# RMP_MAIN.net
KiCad netlist of a schematic drawn in Altium Designer
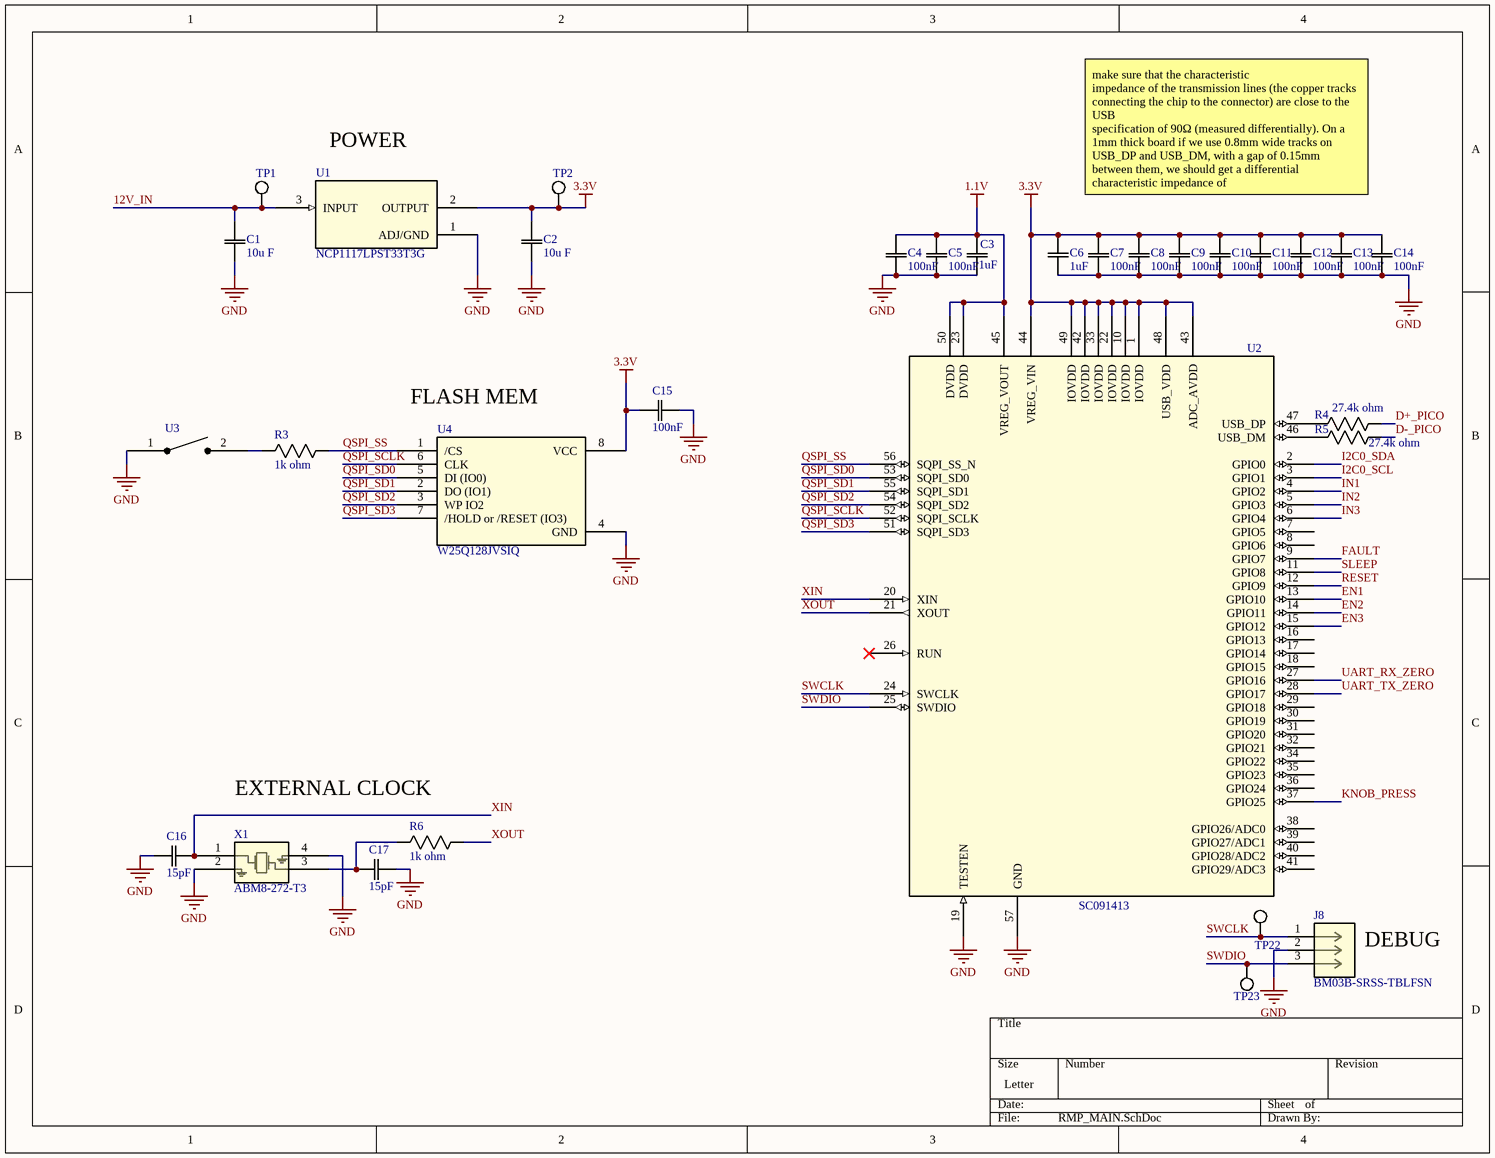
[diagram p0: RMP_MAIN.SchDoc]

(export (version "E")
  (design (tool "Eeschema 10.0.6"))
  (components
    (comp (ref "C1")
      (value "10u F")
      (footprint "G-21_MUR-M")
      (description "10 µF ±10% 16V Ceramic Capacitor X5R 0805 (2012 Metric)")
      (fields (field (name "Comment") "GRM21BR61C106KE15K"))
      (libsource (lib "Schlib1") (part "CAP_GRM21BR61C106KE15K"))
    )
    (comp (ref "C2")
      (value "10u F")
      (footprint "G-21_MUR-M")
      (description "10 µF ±10% 16V Ceramic Capacitor X5R 0805 (2012 Metric)")
      (fields (field (name "Comment") "GRM21BR61C106KE15K"))
      (libsource (lib "Schlib1") (part "CAP_GRM21BR61C106KE15K"))
    )
    (comp (ref "C3")
      (value "1uF")
      (footprint "CAPC17595_90N_KEM-M")
      (description "1 µF ±10% 16V Ceramic Capacitor X7R 0603 (1608 Metric)")
      (fields (field (name "Comment") "C0603C105K4RACTU"))
      (libsource (lib "Schlib1") (part "CAP_C0603C105K4RACTU"))
    )
    (comp (ref "C4")
      (value "100nF")
      (footprint "CC0603N_YAG-M")
      (description "0.1 µF ±10% 16V Ceramic Capacitor X7R 0603 (1608 Metric)")
      (fields (field (name "Comment") "CC0603KRX7R7BB104"))
      (libsource (lib "Schlib1") (part "CAP_CC0603KRX7R7BB104"))
    )
    (comp (ref "C5")
      (value "100nF")
      (footprint "CC0603N_YAG-M")
      (description "0.1 µF ±10% 16V Ceramic Capacitor X7R 0603 (1608 Metric)")
      (fields (field (name "Comment") "CC0603KRX7R7BB104"))
      (libsource (lib "Schlib1") (part "CAP_CC0603KRX7R7BB104"))
    )
    (comp (ref "C6")
      (value "1uF")
      (footprint "CAPC17595_90N_KEM-M")
      (description "1 µF ±10% 16V Ceramic Capacitor X7R 0603 (1608 Metric)")
      (fields (field (name "Comment") "C0603C105K4RACTU"))
      (libsource (lib "Schlib1") (part "CAP_C0603C105K4RACTU"))
    )
    (comp (ref "C7")
      (value "100nF")
      (footprint "CC0603N_YAG-M")
      (description "0.1 µF ±10% 16V Ceramic Capacitor X7R 0603 (1608 Metric)")
      (fields (field (name "Comment") "CC0603KRX7R7BB104"))
      (libsource (lib "Schlib1") (part "CAP_CC0603KRX7R7BB104"))
    )
    (comp (ref "C8")
      (value "100nF")
      (footprint "CC0603N_YAG-M")
      (description "0.1 µF ±10% 16V Ceramic Capacitor X7R 0603 (1608 Metric)")
      (fields (field (name "Comment") "CC0603KRX7R7BB104"))
      (libsource (lib "Schlib1") (part "CAP_CC0603KRX7R7BB104"))
    )
    (comp (ref "C9")
      (value "100nF")
      (footprint "CC0603N_YAG-M")
      (description "0.1 µF ±10% 16V Ceramic Capacitor X7R 0603 (1608 Metric)")
      (fields (field (name "Comment") "CC0603KRX7R7BB104"))
      (libsource (lib "Schlib1") (part "CAP_CC0603KRX7R7BB104"))
    )
    (comp (ref "C10")
      (value "100nF")
      (footprint "CC0603N_YAG-M")
      (description "0.1 µF ±10% 16V Ceramic Capacitor X7R 0603 (1608 Metric)")
      (fields (field (name "Comment") "CC0603KRX7R7BB104"))
      (libsource (lib "Schlib1") (part "CAP_CC0603KRX7R7BB104"))
    )
    (comp (ref "C11")
      (value "100nF")
      (footprint "CC0603N_YAG-M")
      (description "0.1 µF ±10% 16V Ceramic Capacitor X7R 0603 (1608 Metric)")
      (fields (field (name "Comment") "CC0603KRX7R7BB104"))
      (libsource (lib "Schlib1") (part "CAP_CC0603KRX7R7BB104"))
    )
    (comp (ref "C12")
      (value "100nF")
      (footprint "CC0603N_YAG-M")
      (description "0.1 µF ±10% 16V Ceramic Capacitor X7R 0603 (1608 Metric)")
      (fields (field (name "Comment") "CC0603KRX7R7BB104"))
      (libsource (lib "Schlib1") (part "CAP_CC0603KRX7R7BB104"))
    )
    (comp (ref "C13")
      (value "100nF")
      (footprint "CC0603N_YAG-M")
      (description "0.1 µF ±10% 16V Ceramic Capacitor X7R 0603 (1608 Metric)")
      (fields (field (name "Comment") "CC0603KRX7R7BB104"))
      (libsource (lib "Schlib1") (part "CAP_CC0603KRX7R7BB104"))
    )
    (comp (ref "C14")
      (value "100nF")
      (footprint "CC0603N_YAG-M")
      (description "0.1 µF ±10% 16V Ceramic Capacitor X7R 0603 (1608 Metric)")
      (fields (field (name "Comment") "CC0603KRX7R7BB104"))
      (libsource (lib "Schlib1") (part "CAP_CC0603KRX7R7BB104"))
    )
    (comp (ref "C15")
      (value "100nF")
      (footprint "CC0603N_YAG-M")
      (description "0.1 µF ±10% 16V Ceramic Capacitor X7R 0603 (1608 Metric)")
      (fields (field (name "Comment") "CC0603KRX7R7BB104"))
      (libsource (lib "Schlib1") (part "CAP_CC0603KRX7R7BB104"))
    )
    (comp (ref "C16")
      (value "15pF")
      (footprint "CAP_CC0805_YAG-M")
      (description "15 pF ±1% 50V Ceramic Capacitor C0G, NP0 0805 (2012 Metric)")
      (fields (field (name "Comment") "CC0805FRNPO9BN150"))
      (libsource (lib "Schlib1") (part "CAP_CC0805FRNPO9BN150"))
    )
    (comp (ref "C17")
      (value "15pF")
      (footprint "CAP_CC0805_YAG-M")
      (description "15 pF ±1% 50V Ceramic Capacitor C0G, NP0 0805 (2012 Metric)")
      (fields (field (name "Comment") "CC0805FRNPO9BN150"))
      (libsource (lib "Schlib1") (part "CAP_CC0805FRNPO9BN150"))
    )
    (comp (ref "J8")
      (value "BM03B-SRSS-TBLFSN")
      (footprint "CONN_BM03B-SRSS-TBLFSN_JST")
      (description "No Description Available")
      (libsource (lib "Schlib1") (part "BM03B-SRSS-TBLFSN"))
    )
    (comp (ref "R3")
      (value "1k ohm")
      (footprint "RES_RNCF0805_STP-M")
      (description "1 kOhms ±0.5% 0.25W, 1/4W Chip Resistor 0805 (2012 Metric) Automotive AEC-Q200 Thin Film")
      (fields (field (name "Comment") "RNCF0805DTE1K00"))
      (libsource (lib "Schlib1") (part "RES_RNCF0805DTE1K00"))
    )
    (comp (ref "R4")
      (value "27.4k ohm")
      (footprint "RESC1508X55N")
      (description "27.4 kOhms ±1% 0.125W, 1/8W Chip Resistor 0603 (1608 Metric) Anti-Sulfur Thin Film")
      (fields (field (name "Comment") "MCT06030C2742FP500"))
      (libsource (lib "Schlib1") (part "RES_MCT06030C2742FP500"))
    )
    (comp (ref "R5")
      (value "27.4k ohm")
      (footprint "RESC1508X55N")
      (description "27.4 kOhms ±1% 0.125W, 1/8W Chip Resistor 0603 (1608 Metric) Anti-Sulfur Thin Film")
      (fields (field (name "Comment") "MCT06030C2742FP500"))
      (libsource (lib "Schlib1") (part "RES_MCT06030C2742FP500"))
    )
    (comp (ref "R6")
      (value "1k ohm")
      (footprint "RES_RNCF0805_STP-M")
      (description "1 kOhms ±0.5% 0.25W, 1/4W Chip Resistor 0805 (2012 Metric) Automotive AEC-Q200 Thin Film")
      (fields (field (name "Comment") "RNCF0805DTE1K00"))
      (libsource (lib "Schlib1") (part "RES_RNCF0805DTE1K00"))
    )
    (comp (ref "TP1")
      (value "TestPoint")
      (footprint "Testpoint")
      (libsource (lib "Schlib1") (part "TestPoint"))
    )
    (comp (ref "TP2")
      (value "TestPoint")
      (footprint "Testpoint")
      (libsource (lib "Schlib1") (part "TestPoint"))
    )
    (comp (ref "TP22")
      (value "TestPoint")
      (footprint "Testpoint")
      (libsource (lib "Schlib1") (part "TestPoint"))
    )
    (comp (ref "TP23")
      (value "TestPoint")
      (footprint "Testpoint")
      (libsource (lib "Schlib1") (part "TestPoint"))
    )
    (comp (ref "U1")
      (value "NCP1117LPST33T3G")
      (footprint "SOT223-3_ONS-M")
      (description "Linear Voltage Regulator IC Positive Fixed 1 Output 1A SOT-223")
      (libsource (lib "Schlib1") (part "NCP1117LPST33T3G"))
    )
    (comp (ref "U2")
      (value "SC091413")
      (footprint "QFN56_7X7_RPI-M")
      (description "ARM® Cortex®-M0+ - Microcontroller IC 32-Bit Dual-Core 133MHz External Program Memory 56-QFN (7x7)")
      (libsource (lib "Schlib1") (part "SC091413"))
    )
    (comp (ref "U3")
      (value "PTS636SM43SMTR LFS")
      (footprint "PTS636SM43SMTR LFS")
      (description "Tactile Switch SPST-NO Top Actuated Surface Mount")
      (libsource (lib "Schlib1") (part "PTS636SM43SMTR LFS"))
    )
    (comp (ref "U4")
      (value "W25Q128JVSIQ")
      (footprint "SOIC_128JVSIQ_WIN-M")
      (description "FLASH - NOR Memory IC 128Mbit SPI - Quad I/O, QPI 133 MHz 8-SOIC")
      (libsource (lib "Schlib1") (part "W25Q128JVSIQ"))
    )
    (comp (ref "X1")
      (value "ABM8-272-T3")
      (footprint "ABM8-272-T3_ABR")
      (description "12 MHz ±30ppm Crystal 10pF 50 Ohms 4-SMD, No Lead")
      (libsource (lib "Schlib1") (part "ABM8-272-T3"))
    )
  )
  (nets
    (net (code "1") (name "/12V_IN") (class "Default")
      (node (ref "C1") (pin "2") (pinfunction "2_2") (pintype "passive"))
      (node (ref "TP1") (pin "1") (pinfunction "1_1") (pintype "passive"))
      (node (ref "U1") (pin "3") (pinfunction "INPUT_3") (pintype "input"))
    )
    (net (code "2") (name "/D+_PICO") (class "Default")
      (node (ref "R4") (pin "2") (pinfunction "2_2") (pintype "passive"))
    )
    (net (code "3") (name "/D-_PICO") (class "Default")
      (node (ref "R5") (pin "2") (pinfunction "2_2") (pintype "passive"))
    )
    (net (code "4") (name "/EN1") (class "Default")
      (node (ref "U2") (pin "13") (pinfunction "GPIO10_13") (pintype "bidirectional"))
    )
    (net (code "5") (name "/EN2") (class "Default")
      (node (ref "U2") (pin "14") (pinfunction "GPIO11_14") (pintype "bidirectional"))
    )
    (net (code "6") (name "/EN3") (class "Default")
      (node (ref "U2") (pin "15") (pinfunction "GPIO12_15") (pintype "bidirectional"))
    )
    (net (code "7") (name "/FAULT") (class "Default")
      (node (ref "U2") (pin "9") (pinfunction "GPIO7_9") (pintype "bidirectional"))
    )
    (net (code "8") (name "/I2C0_SCL") (class "Default")
      (node (ref "U2") (pin "3") (pinfunction "GPIO1_3") (pintype "bidirectional"))
    )
    (net (code "9") (name "/I2C0_SDA") (class "Default")
      (node (ref "U2") (pin "2") (pinfunction "GPIO0_2") (pintype "bidirectional"))
    )
    (net (code "10") (name "/IN1") (class "Default")
      (node (ref "U2") (pin "4") (pinfunction "GPIO2_4") (pintype "bidirectional"))
    )
    (net (code "11") (name "/IN2") (class "Default")
      (node (ref "U2") (pin "5") (pinfunction "GPIO3_5") (pintype "bidirectional"))
    )
    (net (code "12") (name "/IN3") (class "Default")
      (node (ref "U2") (pin "6") (pinfunction "GPIO4_6") (pintype "bidirectional"))
    )
    (net (code "13") (name "/KNOB_PRESS") (class "Default")
      (node (ref "U2") (pin "37") (pinfunction "GPIO25_37") (pintype "bidirectional"))
    )
    (net (code "14") (name "/QSPI_SCLK") (class "Default")
      (node (ref "U2") (pin "52") (pinfunction "SQPI_SCLK_52") (pintype "bidirectional"))
      (node (ref "U4") (pin "6") (pinfunction "CLK_6") (pintype "passive"))
    )
    (net (code "15") (name "/QSPI_SD0") (class "Default")
      (node (ref "U2") (pin "53") (pinfunction "SQPI_SD0_53") (pintype "bidirectional"))
      (node (ref "U4") (pin "5") (pinfunction "DI_(IO0)_5") (pintype "passive"))
    )
    (net (code "16") (name "/QSPI_SD1") (class "Default")
      (node (ref "U2") (pin "55") (pinfunction "SQPI_SD1_55") (pintype "bidirectional"))
      (node (ref "U4") (pin "2") (pinfunction "DO_(IO1)_2") (pintype "passive"))
    )
    (net (code "17") (name "/QSPI_SD2") (class "Default")
      (node (ref "U2") (pin "54") (pinfunction "SQPI_SD2_54") (pintype "bidirectional"))
      (node (ref "U4") (pin "3") (pinfunction "WP_IO2_3") (pintype "passive"))
    )
    (net (code "18") (name "/QSPI_SD3") (class "Default")
      (node (ref "U2") (pin "51") (pinfunction "SQPI_SD3_51") (pintype "bidirectional"))
      (node (ref "U4") (pin "7") (pinfunction "/HOLD_or_/RESET_(IO3)_7") (pintype "passive"))
    )
    (net (code "19") (name "/QSPI_SS") (class "Default")
      (node (ref "R3") (pin "2") (pinfunction "2_2") (pintype "passive"))
      (node (ref "U2") (pin "56") (pinfunction "SQPI_SS_N_56") (pintype "bidirectional"))
      (node (ref "U4") (pin "1") (pinfunction "/CS_1") (pintype "passive"))
    )
    (net (code "20") (name "/RESET") (class "Default")
      (node (ref "U2") (pin "12") (pinfunction "GPIO9_12") (pintype "bidirectional"))
    )
    (net (code "21") (name "/SLEEP") (class "Default")
      (node (ref "U2") (pin "11") (pinfunction "GPIO8_11") (pintype "bidirectional"))
    )
    (net (code "22") (name "/SWCLK") (class "Default")
      (node (ref "J8") (pin "1") (pinfunction "1_1") (pintype "passive"))
      (node (ref "TP22") (pin "1") (pinfunction "1_1") (pintype "passive"))
      (node (ref "U2") (pin "24") (pinfunction "SWCLK_24") (pintype "input"))
    )
    (net (code "23") (name "/SWDIO") (class "Default")
      (node (ref "J8") (pin "3") (pinfunction "3_3") (pintype "passive"))
      (node (ref "TP23") (pin "1") (pinfunction "1_1") (pintype "passive"))
      (node (ref "U2") (pin "25") (pinfunction "SWDIO_25") (pintype "bidirectional"))
    )
    (net (code "24") (name "/UART_RX_ZERO") (class "Default")
      (node (ref "U2") (pin "27") (pinfunction "GPIO16_27") (pintype "bidirectional"))
    )
    (net (code "25") (name "/UART_TX_ZERO") (class "Default")
      (node (ref "U2") (pin "28") (pinfunction "GPIO17_28") (pintype "bidirectional"))
    )
    (net (code "26") (name "/XIN") (class "Default")
      (node (ref "C16") (pin "2") (pinfunction "2_2") (pintype "passive"))
      (node (ref "U2") (pin "20") (pinfunction "XIN_20") (pintype "input"))
      (node (ref "X1") (pin "1") (pinfunction "1_1") (pintype "passive"))
    )
    (net (code "27") (name "/XOUT") (class "Default")
      (node (ref "R6") (pin "2") (pinfunction "2_2") (pintype "passive"))
      (node (ref "U2") (pin "21") (pinfunction "XOUT_21") (pintype "output"))
    )
    (net (code "28") (name "1.1V") (class "Default")
      (node (ref "C3") (pin "2") (pinfunction "2_2") (pintype "passive"))
      (node (ref "C4") (pin "2") (pinfunction "2_2") (pintype "passive"))
      (node (ref "C5") (pin "2") (pinfunction "2_2") (pintype "passive"))
      (node (ref "U2") (pin "23") (pinfunction "DVDD_23") (pintype "power_in"))
      (node (ref "U2") (pin "45") (pinfunction "VREG_VOUT_45") (pintype "power_in"))
      (node (ref "U2") (pin "50") (pinfunction "DVDD_50") (pintype "power_in"))
    )
    (net (code "29") (name "3.3V") (class "Default")
      (node (ref "C10") (pin "2") (pinfunction "2_2") (pintype "passive"))
      (node (ref "C11") (pin "2") (pinfunction "2_2") (pintype "passive"))
      (node (ref "C12") (pin "2") (pinfunction "2_2") (pintype "passive"))
      (node (ref "C13") (pin "2") (pinfunction "2_2") (pintype "passive"))
      (node (ref "C14") (pin "2") (pinfunction "2_2") (pintype "passive"))
      (node (ref "C15") (pin "2") (pinfunction "2_2") (pintype "passive"))
      (node (ref "C2") (pin "2") (pinfunction "2_2") (pintype "passive"))
      (node (ref "C6") (pin "1") (pinfunction "1_1") (pintype "passive"))
      (node (ref "C7") (pin "2") (pinfunction "2_2") (pintype "passive"))
      (node (ref "C8") (pin "2") (pinfunction "2_2") (pintype "passive"))
      (node (ref "C9") (pin "2") (pinfunction "2_2") (pintype "passive"))
      (node (ref "TP2") (pin "1") (pinfunction "1_1") (pintype "passive"))
      (node (ref "U1") (pin "2") (pinfunction "OUTPUT_2") (pintype "power_in"))
      (node (ref "U2") (pin "1") (pinfunction "IOVDD_1") (pintype "power_in"))
      (node (ref "U2") (pin "10") (pinfunction "IOVDD_10") (pintype "power_in"))
      (node (ref "U2") (pin "22") (pinfunction "IOVDD_22") (pintype "power_in"))
      (node (ref "U2") (pin "33") (pinfunction "IOVDD_33") (pintype "power_in"))
      (node (ref "U2") (pin "42") (pinfunction "IOVDD_42") (pintype "power_in"))
      (node (ref "U2") (pin "43") (pinfunction "ADC_AVDD_43") (pintype "power_in"))
      (node (ref "U2") (pin "44") (pinfunction "VREG_VIN_44") (pintype "power_in"))
      (node (ref "U2") (pin "48") (pinfunction "USB_VDD_48") (pintype "power_in"))
      (node (ref "U2") (pin "49") (pinfunction "IOVDD_49") (pintype "power_in"))
      (node (ref "U4") (pin "8") (pinfunction "VCC_8") (pintype "power_in"))
    )
    (net (code "30") (name "GND") (class "Default")
      (node (ref "C1") (pin "1") (pinfunction "1_1") (pintype "passive"))
      (node (ref "C10") (pin "1") (pinfunction "1_1") (pintype "passive"))
      (node (ref "C11") (pin "1") (pinfunction "1_1") (pintype "passive"))
      (node (ref "C12") (pin "1") (pinfunction "1_1") (pintype "passive"))
      (node (ref "C13") (pin "1") (pinfunction "1_1") (pintype "passive"))
      (node (ref "C14") (pin "1") (pinfunction "1_1") (pintype "passive"))
      (node (ref "C15") (pin "1") (pinfunction "1_1") (pintype "passive"))
      (node (ref "C16") (pin "1") (pinfunction "1_1") (pintype "passive"))
      (node (ref "C17") (pin "2") (pinfunction "2_2") (pintype "passive"))
      (node (ref "C2") (pin "1") (pinfunction "1_1") (pintype "passive"))
      (node (ref "C3") (pin "1") (pinfunction "1_1") (pintype "passive"))
      (node (ref "C4") (pin "1") (pinfunction "1_1") (pintype "passive"))
      (node (ref "C5") (pin "1") (pinfunction "1_1") (pintype "passive"))
      (node (ref "C6") (pin "2") (pinfunction "2_2") (pintype "passive"))
      (node (ref "C7") (pin "1") (pinfunction "1_1") (pintype "passive"))
      (node (ref "C8") (pin "1") (pinfunction "1_1") (pintype "passive"))
      (node (ref "C9") (pin "1") (pinfunction "1_1") (pintype "passive"))
      (node (ref "J8") (pin "2") (pinfunction "2_2") (pintype "passive"))
      (node (ref "U1") (pin "1") (pinfunction "ADJ/GND_1") (pintype "power_in"))
      (node (ref "U2") (pin "19") (pinfunction "TESTEN_19") (pintype "input"))
      (node (ref "U2") (pin "57") (pinfunction "GND_57") (pintype "power_in"))
      (node (ref "U3") (pin "1") (pinfunction "1_1") (pintype "passive"))
      (node (ref "U4") (pin "4") (pinfunction "GND_4") (pintype "power_in"))
      (node (ref "X1") (pin "2") (pinfunction "2_2") (pintype "passive"))
      (node (ref "X1") (pin "4") (pinfunction "4_4") (pintype "passive"))
    )
    (net (code "31") (name "Net-(C17-Pad1)") (class "Default")
      (node (ref "C17") (pin "1") (pinfunction "1_1") (pintype "passive"))
      (node (ref "R6") (pin "1") (pinfunction "1_1") (pintype "passive"))
      (node (ref "X1") (pin "3") (pinfunction "3_3") (pintype "passive"))
    )
    (net (code "32") (name "Net-(R3-Pad1)") (class "Default")
      (node (ref "R3") (pin "1") (pinfunction "1_1") (pintype "passive"))
      (node (ref "U3") (pin "2") (pinfunction "2_2") (pintype "passive"))
    )
    (net (code "33") (name "Net-(U2-USB_DM)") (class "Default")
      (node (ref "R5") (pin "1") (pinfunction "1_1") (pintype "passive"))
      (node (ref "U2") (pin "46") (pinfunction "USB_DM_46") (pintype "bidirectional"))
    )
    (net (code "34") (name "Net-(U2-USB_DP)") (class "Default")
      (node (ref "R4") (pin "1") (pinfunction "1_1") (pintype "passive"))
      (node (ref "U2") (pin "47") (pinfunction "USB_DP_47") (pintype "bidirectional"))
    )
    (net (code "35") (name "unconnected-(U2-GPIO5-Pad7)") (class "Default")
      (node (ref "U2") (pin "7") (pinfunction "GPIO5_7") (pintype "bidirectional"))
    )
    (net (code "36") (name "unconnected-(U2-GPIO6-Pad8)") (class "Default")
      (node (ref "U2") (pin "8") (pinfunction "GPIO6_8") (pintype "bidirectional"))
    )
    (net (code "37") (name "unconnected-(U2-GPIO13-Pad16)") (class "Default")
      (node (ref "U2") (pin "16") (pinfunction "GPIO13_16") (pintype "bidirectional"))
    )
    (net (code "38") (name "unconnected-(U2-GPIO14-Pad17)") (class "Default")
      (node (ref "U2") (pin "17") (pinfunction "GPIO14_17") (pintype "bidirectional"))
    )
    (net (code "39") (name "unconnected-(U2-GPIO15-Pad18)") (class "Default")
      (node (ref "U2") (pin "18") (pinfunction "GPIO15_18") (pintype "bidirectional"))
    )
    (net (code "40") (name "unconnected-(U2-GPIO18-Pad29)") (class "Default")
      (node (ref "U2") (pin "29") (pinfunction "GPIO18_29") (pintype "bidirectional"))
    )
    (net (code "41") (name "unconnected-(U2-GPIO19-Pad30)") (class "Default")
      (node (ref "U2") (pin "30") (pinfunction "GPIO19_30") (pintype "bidirectional"))
    )
    (net (code "42") (name "unconnected-(U2-GPIO20-Pad31)") (class "Default")
      (node (ref "U2") (pin "31") (pinfunction "GPIO20_31") (pintype "bidirectional"))
    )
    (net (code "43") (name "unconnected-(U2-GPIO21-Pad32)") (class "Default")
      (node (ref "U2") (pin "32") (pinfunction "GPIO21_32") (pintype "bidirectional"))
    )
    (net (code "44") (name "unconnected-(U2-GPIO22-Pad34)") (class "Default")
      (node (ref "U2") (pin "34") (pinfunction "GPIO22_34") (pintype "bidirectional"))
    )
    (net (code "45") (name "unconnected-(U2-GPIO23-Pad35)") (class "Default")
      (node (ref "U2") (pin "35") (pinfunction "GPIO23_35") (pintype "bidirectional"))
    )
    (net (code "46") (name "unconnected-(U2-GPIO24-Pad36)") (class "Default")
      (node (ref "U2") (pin "36") (pinfunction "GPIO24_36") (pintype "bidirectional"))
    )
    (net (code "47") (name "unconnected-(U2-GPIO26{slash}ADC0-Pad38)") (class "Default")
      (node (ref "U2") (pin "38") (pinfunction "GPIO26/ADC0_38") (pintype "bidirectional"))
    )
    (net (code "48") (name "unconnected-(U2-GPIO27{slash}ADC1-Pad39)") (class "Default")
      (node (ref "U2") (pin "39") (pinfunction "GPIO27/ADC1_39") (pintype "bidirectional"))
    )
    (net (code "49") (name "unconnected-(U2-GPIO28{slash}ADC2-Pad40)") (class "Default")
      (node (ref "U2") (pin "40") (pinfunction "GPIO28/ADC2_40") (pintype "bidirectional"))
    )
    (net (code "50") (name "unconnected-(U2-GPIO29{slash}ADC3-Pad41)") (class "Default")
      (node (ref "U2") (pin "41") (pinfunction "GPIO29/ADC3_41") (pintype "bidirectional"))
    )
    (net (code "51") (name "unconnected-(U2-RUN-Pad26)") (class "Default")
      (node (ref "U2") (pin "26") (pinfunction "RUN_26") (pintype "input+no_connect"))
    )
  )
)
